# NovsSMTBlinkyRevD.net
KiCad netlist of a schematic drawn in EAGLE
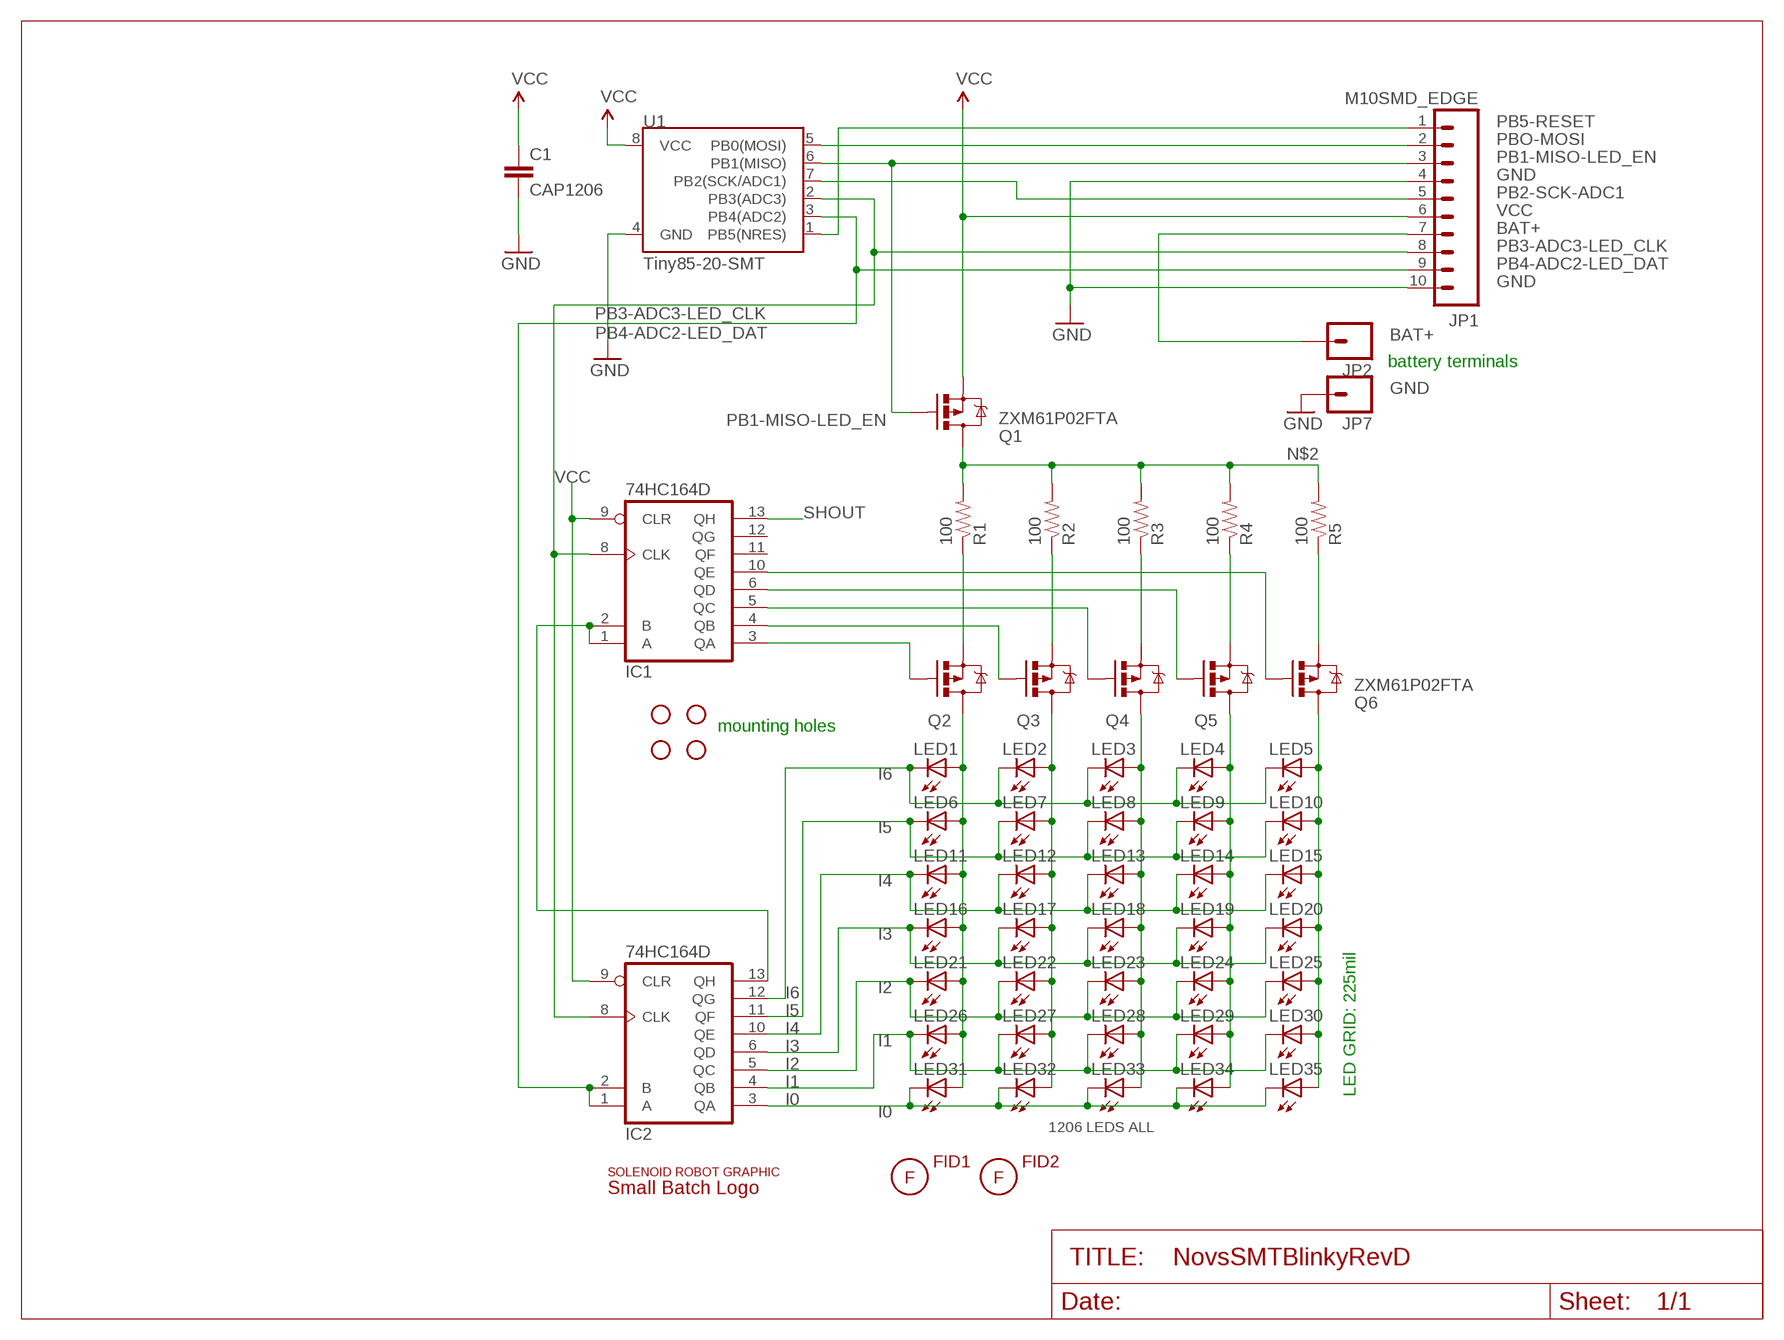
[diagram p0: schematic, sheet 1]

(export (version "E")
  (design (tool "Eeschema 10.0.6"))
  (components
    (comp (ref "C1")
      (value "CAP1206")
      (footprint "eagle-import:1206")
      (libsource (lib "eagle-import") (part "CAP1206"))
    )
    (comp (ref "FID1")
      (value "FIDUCIAL")
      (footprint "eagle-import:FID05MM")
      (libsource (lib "eagle-import") (part "FIDUCIAL"))
    )
    (comp (ref "FID2")
      (value "FIDUCIAL")
      (footprint "eagle-import:FID05MM")
      (libsource (lib "eagle-import") (part "FIDUCIAL"))
    )
    (comp (ref "IC1")
      (value "74HC164D")
      (footprint "eagle-import:SO14")
      (libsource (lib "eagle-import") (part "74164DHC"))
    )
    (comp (ref "IC2")
      (value "74HC164D")
      (footprint "eagle-import:SO14")
      (libsource (lib "eagle-import") (part "74164DHC"))
    )
    (comp (ref "JP1")
      (value "M10SMD_EDGE")
      (footprint "eagle-import:1X10_SMD_EDGE")
      (libsource (lib "eagle-import") (part "M10SMD_EDGE"))
    )
    (comp (ref "JP2")
      (value "M01NOSILK-KIT")
      (footprint "eagle-import:1X01NS-KIT")
      (libsource (lib "eagle-import") (part "M01NOSILK-KIT"))
    )
    (comp (ref "JP3")
      (value "MTGHOLE110MIL")
      (footprint "eagle-import:HOLE112")
      (libsource (lib "eagle-import") (part "MTGHOLE110MIL"))
    )
    (comp (ref "JP4")
      (value "MTGHOLE110MIL")
      (footprint "eagle-import:HOLE112")
      (libsource (lib "eagle-import") (part "MTGHOLE110MIL"))
    )
    (comp (ref "JP5")
      (value "MTGHOLE110MIL")
      (footprint "eagle-import:HOLE112")
      (libsource (lib "eagle-import") (part "MTGHOLE110MIL"))
    )
    (comp (ref "JP6")
      (value "MTGHOLE110MIL")
      (footprint "eagle-import:HOLE112")
      (libsource (lib "eagle-import") (part "MTGHOLE110MIL"))
    )
    (comp (ref "JP7")
      (value "M01NOSILK-KIT")
      (footprint "eagle-import:1X01NS-KIT")
      (libsource (lib "eagle-import") (part "M01NOSILK-KIT"))
    )
    (comp (ref "LED1")
      (value "LED1206")
      (footprint "eagle-import:LED-1206")
      (libsource (lib "eagle-import") (part "LED1206"))
    )
    (comp (ref "LED2")
      (value "LED1206")
      (footprint "eagle-import:LED-1206")
      (libsource (lib "eagle-import") (part "LED1206"))
    )
    (comp (ref "LED3")
      (value "LED1206")
      (footprint "eagle-import:LED-1206")
      (libsource (lib "eagle-import") (part "LED1206"))
    )
    (comp (ref "LED4")
      (value "LED1206")
      (footprint "eagle-import:LED-1206")
      (libsource (lib "eagle-import") (part "LED1206"))
    )
    (comp (ref "LED5")
      (value "LED1206")
      (footprint "eagle-import:LED-1206")
      (libsource (lib "eagle-import") (part "LED1206"))
    )
    (comp (ref "LED6")
      (value "LED1206")
      (footprint "eagle-import:LED-1206")
      (libsource (lib "eagle-import") (part "LED1206"))
    )
    (comp (ref "LED7")
      (value "LED1206")
      (footprint "eagle-import:LED-1206")
      (libsource (lib "eagle-import") (part "LED1206"))
    )
    (comp (ref "LED8")
      (value "LED1206")
      (footprint "eagle-import:LED-1206")
      (libsource (lib "eagle-import") (part "LED1206"))
    )
    (comp (ref "LED9")
      (value "LED1206")
      (footprint "eagle-import:LED-1206")
      (libsource (lib "eagle-import") (part "LED1206"))
    )
    (comp (ref "LED10")
      (value "LED1206")
      (footprint "eagle-import:LED-1206")
      (libsource (lib "eagle-import") (part "LED1206"))
    )
    (comp (ref "LED11")
      (value "LED1206")
      (footprint "eagle-import:LED-1206")
      (libsource (lib "eagle-import") (part "LED1206"))
    )
    (comp (ref "LED12")
      (value "LED1206")
      (footprint "eagle-import:LED-1206")
      (libsource (lib "eagle-import") (part "LED1206"))
    )
    (comp (ref "LED13")
      (value "LED1206")
      (footprint "eagle-import:LED-1206")
      (libsource (lib "eagle-import") (part "LED1206"))
    )
    (comp (ref "LED14")
      (value "LED1206")
      (footprint "eagle-import:LED-1206")
      (libsource (lib "eagle-import") (part "LED1206"))
    )
    (comp (ref "LED15")
      (value "LED1206")
      (footprint "eagle-import:LED-1206")
      (libsource (lib "eagle-import") (part "LED1206"))
    )
    (comp (ref "LED16")
      (value "LED1206")
      (footprint "eagle-import:LED-1206")
      (libsource (lib "eagle-import") (part "LED1206"))
    )
    (comp (ref "LED17")
      (value "LED1206")
      (footprint "eagle-import:LED-1206")
      (libsource (lib "eagle-import") (part "LED1206"))
    )
    (comp (ref "LED18")
      (value "LED1206")
      (footprint "eagle-import:LED-1206")
      (libsource (lib "eagle-import") (part "LED1206"))
    )
    (comp (ref "LED19")
      (value "LED1206")
      (footprint "eagle-import:LED-1206")
      (libsource (lib "eagle-import") (part "LED1206"))
    )
    (comp (ref "LED20")
      (value "LED1206")
      (footprint "eagle-import:LED-1206")
      (libsource (lib "eagle-import") (part "LED1206"))
    )
    (comp (ref "LED21")
      (value "LED1206")
      (footprint "eagle-import:LED-1206")
      (libsource (lib "eagle-import") (part "LED1206"))
    )
    (comp (ref "LED22")
      (value "LED1206")
      (footprint "eagle-import:LED-1206")
      (libsource (lib "eagle-import") (part "LED1206"))
    )
    (comp (ref "LED23")
      (value "LED1206")
      (footprint "eagle-import:LED-1206")
      (libsource (lib "eagle-import") (part "LED1206"))
    )
    (comp (ref "LED24")
      (value "LED1206")
      (footprint "eagle-import:LED-1206")
      (libsource (lib "eagle-import") (part "LED1206"))
    )
    (comp (ref "LED25")
      (value "LED1206")
      (footprint "eagle-import:LED-1206")
      (libsource (lib "eagle-import") (part "LED1206"))
    )
    (comp (ref "LED26")
      (value "LED1206")
      (footprint "eagle-import:LED-1206")
      (libsource (lib "eagle-import") (part "LED1206"))
    )
    (comp (ref "LED27")
      (value "LED1206")
      (footprint "eagle-import:LED-1206")
      (libsource (lib "eagle-import") (part "LED1206"))
    )
    (comp (ref "LED28")
      (value "LED1206")
      (footprint "eagle-import:LED-1206")
      (libsource (lib "eagle-import") (part "LED1206"))
    )
    (comp (ref "LED29")
      (value "LED1206")
      (footprint "eagle-import:LED-1206")
      (libsource (lib "eagle-import") (part "LED1206"))
    )
    (comp (ref "LED30")
      (value "LED1206")
      (footprint "eagle-import:LED-1206")
      (libsource (lib "eagle-import") (part "LED1206"))
    )
    (comp (ref "LED31")
      (value "LED1206")
      (footprint "eagle-import:LED-1206")
      (libsource (lib "eagle-import") (part "LED1206"))
    )
    (comp (ref "LED32")
      (value "LED1206")
      (footprint "eagle-import:LED-1206")
      (libsource (lib "eagle-import") (part "LED1206"))
    )
    (comp (ref "LED33")
      (value "LED1206")
      (footprint "eagle-import:LED-1206")
      (libsource (lib "eagle-import") (part "LED1206"))
    )
    (comp (ref "LED34")
      (value "LED1206")
      (footprint "eagle-import:LED-1206")
      (libsource (lib "eagle-import") (part "LED1206"))
    )
    (comp (ref "LED35")
      (value "LED1206")
      (footprint "eagle-import:LED-1206")
      (libsource (lib "eagle-import") (part "LED1206"))
    )
    (comp (ref "Q1")
      (value "ZXM61P02FTA")
      (footprint "eagle-import:SOT23-3")
      (libsource (lib "eagle-import") (part "MOSFET-PCHANNELSMD"))
    )
    (comp (ref "Q2")
      (value "MOSFET-PCHANNELSMD")
      (footprint "eagle-import:SOT23-3")
      (libsource (lib "eagle-import") (part "MOSFET-PCHANNELSMD"))
    )
    (comp (ref "Q3")
      (value "MOSFET-PCHANNELSMD")
      (footprint "eagle-import:SOT23-3")
      (libsource (lib "eagle-import") (part "MOSFET-PCHANNELSMD"))
    )
    (comp (ref "Q4")
      (value "MOSFET-PCHANNELSMD")
      (footprint "eagle-import:SOT23-3")
      (libsource (lib "eagle-import") (part "MOSFET-PCHANNELSMD"))
    )
    (comp (ref "Q5")
      (value "MOSFET-PCHANNELSMD")
      (footprint "eagle-import:SOT23-3")
      (libsource (lib "eagle-import") (part "MOSFET-PCHANNELSMD"))
    )
    (comp (ref "Q6")
      (value "ZXM61P02FTA")
      (footprint "eagle-import:SOT23-3")
      (libsource (lib "eagle-import") (part "MOSFET-PCHANNELSMD"))
    )
    (comp (ref "R1")
      (value "100")
      (footprint "eagle-import:1206")
      (libsource (lib "eagle-import") (part "RES1206"))
    )
    (comp (ref "R2")
      (value "100")
      (footprint "eagle-import:1206")
      (libsource (lib "eagle-import") (part "RES1206"))
    )
    (comp (ref "R3")
      (value "100")
      (footprint "eagle-import:1206")
      (libsource (lib "eagle-import") (part "RES1206"))
    )
    (comp (ref "R4")
      (value "100")
      (footprint "eagle-import:1206")
      (libsource (lib "eagle-import") (part "RES1206"))
    )
    (comp (ref "R5")
      (value "100")
      (footprint "eagle-import:1206")
      (libsource (lib "eagle-import") (part "RES1206"))
    )
    (comp (ref "U$1")
      (value "SOLENOID_ROBOT")
      (footprint "eagle-import:SOLENOID_ROBT_450MIL")
      (libsource (lib "eagle-import") (part "SOLENOID_ROBOT"))
    )
    (comp (ref "U$4")
      (value "SMALLBATCH_LOGO750W")
      (footprint "eagle-import:SMALLBATCH_750W")
      (libsource (lib "eagle-import") (part "SMALLBATCH_LOGO750W"))
    )
    (comp (ref "U1")
      (value "Tiny85-20-SMT")
      (footprint "eagle-import:SO08-EIAJ")
      (libsource (lib "eagle-import") (part "ATTINY45TINY85-20-SMT"))
    )
  )
  (nets
    (net (code "1") (name "/BAT+") (class "Default")
      (node (ref "JP1") (pin "7") (pinfunction "7_7") (pintype "passive"))
      (node (ref "JP2") (pin "1") (pinfunction "1_1") (pintype "passive"))
    )
    (net (code "2") (name "/I0") (class "Default")
      (node (ref "IC2") (pin "3") (pinfunction "QA_3") (pintype "output"))
      (node (ref "LED31") (pin "C") (pinfunction "C_C") (pintype "passive"))
      (node (ref "LED32") (pin "C") (pinfunction "C_C") (pintype "passive"))
      (node (ref "LED33") (pin "C") (pinfunction "C_C") (pintype "passive"))
      (node (ref "LED34") (pin "C") (pinfunction "C_C") (pintype "passive"))
      (node (ref "LED35") (pin "C") (pinfunction "C_C") (pintype "passive"))
    )
    (net (code "3") (name "/I1") (class "Default")
      (node (ref "IC2") (pin "4") (pinfunction "QB_4") (pintype "output"))
      (node (ref "LED26") (pin "C") (pinfunction "C_C") (pintype "passive"))
      (node (ref "LED27") (pin "C") (pinfunction "C_C") (pintype "passive"))
      (node (ref "LED28") (pin "C") (pinfunction "C_C") (pintype "passive"))
      (node (ref "LED29") (pin "C") (pinfunction "C_C") (pintype "passive"))
      (node (ref "LED30") (pin "C") (pinfunction "C_C") (pintype "passive"))
    )
    (net (code "4") (name "/I2") (class "Default")
      (node (ref "IC2") (pin "5") (pinfunction "QC_5") (pintype "output"))
      (node (ref "LED21") (pin "C") (pinfunction "C_C") (pintype "passive"))
      (node (ref "LED22") (pin "C") (pinfunction "C_C") (pintype "passive"))
      (node (ref "LED23") (pin "C") (pinfunction "C_C") (pintype "passive"))
      (node (ref "LED24") (pin "C") (pinfunction "C_C") (pintype "passive"))
      (node (ref "LED25") (pin "C") (pinfunction "C_C") (pintype "passive"))
    )
    (net (code "5") (name "/I3") (class "Default")
      (node (ref "IC2") (pin "6") (pinfunction "QD_6") (pintype "output"))
      (node (ref "LED16") (pin "C") (pinfunction "C_C") (pintype "passive"))
      (node (ref "LED17") (pin "C") (pinfunction "C_C") (pintype "passive"))
      (node (ref "LED18") (pin "C") (pinfunction "C_C") (pintype "passive"))
      (node (ref "LED19") (pin "C") (pinfunction "C_C") (pintype "passive"))
      (node (ref "LED20") (pin "C") (pinfunction "C_C") (pintype "passive"))
    )
    (net (code "6") (name "/I4") (class "Default")
      (node (ref "IC2") (pin "10") (pinfunction "QE_10") (pintype "output"))
      (node (ref "LED11") (pin "C") (pinfunction "C_C") (pintype "passive"))
      (node (ref "LED12") (pin "C") (pinfunction "C_C") (pintype "passive"))
      (node (ref "LED13") (pin "C") (pinfunction "C_C") (pintype "passive"))
      (node (ref "LED14") (pin "C") (pinfunction "C_C") (pintype "passive"))
      (node (ref "LED15") (pin "C") (pinfunction "C_C") (pintype "passive"))
    )
    (net (code "7") (name "/I5") (class "Default")
      (node (ref "IC2") (pin "11") (pinfunction "QF_11") (pintype "output"))
      (node (ref "LED10") (pin "C") (pinfunction "C_C") (pintype "passive"))
      (node (ref "LED6") (pin "C") (pinfunction "C_C") (pintype "passive"))
      (node (ref "LED7") (pin "C") (pinfunction "C_C") (pintype "passive"))
      (node (ref "LED8") (pin "C") (pinfunction "C_C") (pintype "passive"))
      (node (ref "LED9") (pin "C") (pinfunction "C_C") (pintype "passive"))
    )
    (net (code "8") (name "/I6") (class "Default")
      (node (ref "IC2") (pin "12") (pinfunction "QG_12") (pintype "output"))
      (node (ref "LED1") (pin "C") (pinfunction "C_C") (pintype "passive"))
      (node (ref "LED2") (pin "C") (pinfunction "C_C") (pintype "passive"))
      (node (ref "LED3") (pin "C") (pinfunction "C_C") (pintype "passive"))
      (node (ref "LED4") (pin "C") (pinfunction "C_C") (pintype "passive"))
      (node (ref "LED5") (pin "C") (pinfunction "C_C") (pintype "passive"))
    )
    (net (code "9") (name "/N$2") (class "Default")
      (node (ref "Q1") (pin "3") (pinfunction "D_3") (pintype "passive"))
      (node (ref "R1") (pin "2") (pinfunction "2_2") (pintype "passive"))
      (node (ref "R2") (pin "2") (pinfunction "2_2") (pintype "passive"))
      (node (ref "R3") (pin "2") (pinfunction "2_2") (pintype "passive"))
      (node (ref "R4") (pin "2") (pinfunction "2_2") (pintype "passive"))
      (node (ref "R5") (pin "2") (pinfunction "2_2") (pintype "passive"))
    )
    (net (code "10") (name "/PB1-MISO-LED_EN") (class "Default")
      (node (ref "JP1") (pin "3") (pinfunction "3_3") (pintype "passive"))
      (node (ref "Q1") (pin "1") (pinfunction "G_1") (pintype "passive"))
      (node (ref "U1") (pin "6") (pinfunction "PB1(MISO)_6") (pintype "bidirectional"))
    )
    (net (code "11") (name "/PB2-SCK-ADC1") (class "Default")
      (node (ref "JP1") (pin "5") (pinfunction "5_5") (pintype "passive"))
      (node (ref "U1") (pin "7") (pinfunction "PB2(SCK/ADC1)_7") (pintype "bidirectional"))
    )
    (net (code "12") (name "/PB3-ADC3-LED_CLK") (class "Default")
      (node (ref "IC1") (pin "8") (pinfunction "CLK_8") (pintype "input"))
      (node (ref "IC2") (pin "8") (pinfunction "CLK_8") (pintype "input"))
      (node (ref "JP1") (pin "8") (pinfunction "8_8") (pintype "passive"))
      (node (ref "U1") (pin "2") (pinfunction "PB3(ADC3)_2") (pintype "bidirectional"))
    )
    (net (code "13") (name "/PB4-ADC2-LED_DAT") (class "Default")
      (node (ref "IC2") (pin "1") (pinfunction "A_1") (pintype "input"))
      (node (ref "IC2") (pin "2") (pinfunction "B_2") (pintype "input"))
      (node (ref "JP1") (pin "9") (pinfunction "9_9") (pintype "passive"))
      (node (ref "U1") (pin "3") (pinfunction "PB4(ADC2)_3") (pintype "bidirectional"))
    )
    (net (code "14") (name "/PB5-RESET") (class "Default")
      (node (ref "JP1") (pin "1") (pinfunction "1_1") (pintype "passive"))
      (node (ref "U1") (pin "1") (pinfunction "PB5(NRES)_1") (pintype "bidirectional"))
    )
    (net (code "15") (name "/PBO-MOSI") (class "Default")
      (node (ref "JP1") (pin "2") (pinfunction "2_2") (pintype "passive"))
      (node (ref "U1") (pin "5") (pinfunction "PB0(MOSI)_5") (pintype "bidirectional"))
    )
    (net (code "16") (name "/SHOUT") (class "Default")
      (node (ref "IC1") (pin "13") (pinfunction "QH_13") (pintype "output"))
    )
    (net (code "17") (name "GND") (class "Default")
      (node (ref "C1") (pin "2") (pinfunction "2_2") (pintype "passive"))
      (node (ref "JP1") (pin "10") (pinfunction "10_10") (pintype "passive"))
      (node (ref "JP1") (pin "4") (pinfunction "4_4") (pintype "passive"))
      (node (ref "JP7") (pin "1") (pinfunction "1_1") (pintype "passive"))
      (node (ref "U1") (pin "4") (pinfunction "GND_4") (pintype "bidirectional"))
    )
    (net (code "18") (name "Net-(IC1A-A)") (class "Default")
      (node (ref "IC1") (pin "1") (pinfunction "A_1") (pintype "input"))
      (node (ref "IC1") (pin "2") (pinfunction "B_2") (pintype "input"))
      (node (ref "IC2") (pin "13") (pinfunction "QH_13") (pintype "output"))
    )
    (net (code "19") (name "Net-(IC1A-QA)") (class "Default")
      (node (ref "IC1") (pin "3") (pinfunction "QA_3") (pintype "output"))
      (node (ref "Q2") (pin "1") (pinfunction "G_1") (pintype "passive"))
    )
    (net (code "20") (name "Net-(IC1A-QB)") (class "Default")
      (node (ref "IC1") (pin "4") (pinfunction "QB_4") (pintype "output"))
      (node (ref "Q3") (pin "1") (pinfunction "G_1") (pintype "passive"))
    )
    (net (code "21") (name "Net-(IC1A-QC)") (class "Default")
      (node (ref "IC1") (pin "5") (pinfunction "QC_5") (pintype "output"))
      (node (ref "Q4") (pin "1") (pinfunction "G_1") (pintype "passive"))
    )
    (net (code "22") (name "Net-(IC1A-QD)") (class "Default")
      (node (ref "IC1") (pin "6") (pinfunction "QD_6") (pintype "output"))
      (node (ref "Q5") (pin "1") (pinfunction "G_1") (pintype "passive"))
    )
    (net (code "23") (name "Net-(IC1A-QE)") (class "Default")
      (node (ref "IC1") (pin "10") (pinfunction "QE_10") (pintype "output"))
      (node (ref "Q6") (pin "1") (pinfunction "G_1") (pintype "passive"))
    )
    (net (code "24") (name "Net-(Q2-D)") (class "Default")
      (node (ref "LED1") (pin "A") (pinfunction "A_A") (pintype "passive"))
      (node (ref "LED11") (pin "A") (pinfunction "A_A") (pintype "passive"))
      (node (ref "LED16") (pin "A") (pinfunction "A_A") (pintype "passive"))
      (node (ref "LED21") (pin "A") (pinfunction "A_A") (pintype "passive"))
      (node (ref "LED26") (pin "A") (pinfunction "A_A") (pintype "passive"))
      (node (ref "LED31") (pin "A") (pinfunction "A_A") (pintype "passive"))
      (node (ref "LED6") (pin "A") (pinfunction "A_A") (pintype "passive"))
      (node (ref "Q2") (pin "3") (pinfunction "D_3") (pintype "passive"))
    )
    (net (code "25") (name "Net-(Q2-S)") (class "Default")
      (node (ref "Q2") (pin "2") (pinfunction "S_2") (pintype "passive"))
      (node (ref "R1") (pin "1") (pinfunction "1_1") (pintype "passive"))
    )
    (net (code "26") (name "Net-(Q3-D)") (class "Default")
      (node (ref "LED12") (pin "A") (pinfunction "A_A") (pintype "passive"))
      (node (ref "LED17") (pin "A") (pinfunction "A_A") (pintype "passive"))
      (node (ref "LED2") (pin "A") (pinfunction "A_A") (pintype "passive"))
      (node (ref "LED22") (pin "A") (pinfunction "A_A") (pintype "passive"))
      (node (ref "LED27") (pin "A") (pinfunction "A_A") (pintype "passive"))
      (node (ref "LED32") (pin "A") (pinfunction "A_A") (pintype "passive"))
      (node (ref "LED7") (pin "A") (pinfunction "A_A") (pintype "passive"))
      (node (ref "Q3") (pin "3") (pinfunction "D_3") (pintype "passive"))
    )
    (net (code "27") (name "Net-(Q3-S)") (class "Default")
      (node (ref "Q3") (pin "2") (pinfunction "S_2") (pintype "passive"))
      (node (ref "R2") (pin "1") (pinfunction "1_1") (pintype "passive"))
    )
    (net (code "28") (name "Net-(Q4-D)") (class "Default")
      (node (ref "LED13") (pin "A") (pinfunction "A_A") (pintype "passive"))
      (node (ref "LED18") (pin "A") (pinfunction "A_A") (pintype "passive"))
      (node (ref "LED23") (pin "A") (pinfunction "A_A") (pintype "passive"))
      (node (ref "LED28") (pin "A") (pinfunction "A_A") (pintype "passive"))
      (node (ref "LED3") (pin "A") (pinfunction "A_A") (pintype "passive"))
      (node (ref "LED33") (pin "A") (pinfunction "A_A") (pintype "passive"))
      (node (ref "LED8") (pin "A") (pinfunction "A_A") (pintype "passive"))
      (node (ref "Q4") (pin "3") (pinfunction "D_3") (pintype "passive"))
    )
    (net (code "29") (name "Net-(Q4-S)") (class "Default")
      (node (ref "Q4") (pin "2") (pinfunction "S_2") (pintype "passive"))
      (node (ref "R3") (pin "1") (pinfunction "1_1") (pintype "passive"))
    )
    (net (code "30") (name "Net-(Q5-D)") (class "Default")
      (node (ref "LED14") (pin "A") (pinfunction "A_A") (pintype "passive"))
      (node (ref "LED19") (pin "A") (pinfunction "A_A") (pintype "passive"))
      (node (ref "LED24") (pin "A") (pinfunction "A_A") (pintype "passive"))
      (node (ref "LED29") (pin "A") (pinfunction "A_A") (pintype "passive"))
      (node (ref "LED34") (pin "A") (pinfunction "A_A") (pintype "passive"))
      (node (ref "LED4") (pin "A") (pinfunction "A_A") (pintype "passive"))
      (node (ref "LED9") (pin "A") (pinfunction "A_A") (pintype "passive"))
      (node (ref "Q5") (pin "3") (pinfunction "D_3") (pintype "passive"))
    )
    (net (code "31") (name "Net-(Q5-S)") (class "Default")
      (node (ref "Q5") (pin "2") (pinfunction "S_2") (pintype "passive"))
      (node (ref "R4") (pin "1") (pinfunction "1_1") (pintype "passive"))
    )
    (net (code "32") (name "Net-(Q6-D)") (class "Default")
      (node (ref "LED10") (pin "A") (pinfunction "A_A") (pintype "passive"))
      (node (ref "LED15") (pin "A") (pinfunction "A_A") (pintype "passive"))
      (node (ref "LED20") (pin "A") (pinfunction "A_A") (pintype "passive"))
      (node (ref "LED25") (pin "A") (pinfunction "A_A") (pintype "passive"))
      (node (ref "LED30") (pin "A") (pinfunction "A_A") (pintype "passive"))
      (node (ref "LED35") (pin "A") (pinfunction "A_A") (pintype "passive"))
      (node (ref "LED5") (pin "A") (pinfunction "A_A") (pintype "passive"))
      (node (ref "Q6") (pin "3") (pinfunction "D_3") (pintype "passive"))
    )
    (net (code "33") (name "Net-(Q6-S)") (class "Default")
      (node (ref "Q6") (pin "2") (pinfunction "S_2") (pintype "passive"))
      (node (ref "R5") (pin "1") (pinfunction "1_1") (pintype "passive"))
    )
    (net (code "34") (name "VCC") (class "Default")
      (node (ref "C1") (pin "1") (pinfunction "1_1") (pintype "passive"))
      (node (ref "IC1") (pin "9") (pinfunction "CLR_9") (pintype "input"))
      (node (ref "IC2") (pin "9") (pinfunction "CLR_9") (pintype "input"))
      (node (ref "JP1") (pin "6") (pinfunction "6_6") (pintype "passive"))
      (node (ref "Q1") (pin "2") (pinfunction "S_2") (pintype "passive"))
      (node (ref "U1") (pin "8") (pinfunction "VCC_8") (pintype "bidirectional"))
    )
    (net (code "35") (name "unconnected-(IC1A-QF-Pad11)") (class "Default")
      (node (ref "IC1") (pin "11") (pinfunction "QF_11") (pintype "output"))
    )
    (net (code "36") (name "unconnected-(IC1A-QG-Pad12)") (class "Default")
      (node (ref "IC1") (pin "12") (pinfunction "QG_12") (pintype "output"))
    )
  )
)
